# RJ-45_v1_1.net
KiCad netlist of a schematic drawn in EAGLE
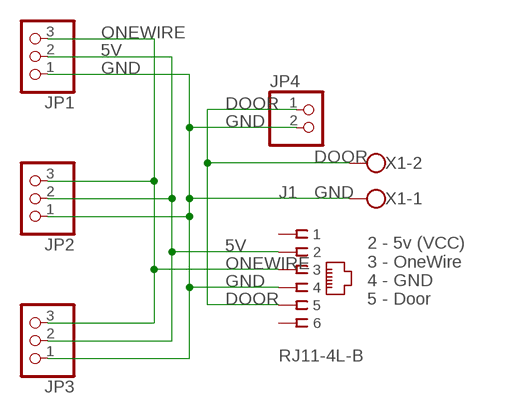
[diagram p0: schematic, sheet 1]

(export (version "E")
  (design (tool "Eeschema 10.0.6"))
  (components
    (comp (ref "J1")
      (value "RJ11-4L-B")
      (footprint "eagle-import:RJ11-NO_SHIELD")
      (fields (field (name "MF") "TYCO ELECTRONICS"))
      (libsource (lib "eagle-import") (part "RJ11-4L-B"))
    )
    (comp (ref "JP1")
      (value "PINHD-1X3")
      (footprint "eagle-import:1X03")
      (libsource (lib "eagle-import") (part "PINHD-1X3"))
    )
    (comp (ref "JP2")
      (value "PINHD-1X3")
      (footprint "eagle-import:1X03")
      (libsource (lib "eagle-import") (part "PINHD-1X3"))
    )
    (comp (ref "JP3")
      (value "PINHD-1X3")
      (footprint "eagle-import:1X03")
      (libsource (lib "eagle-import") (part "PINHD-1X3"))
    )
    (comp (ref "JP4")
      (value "PINHD-1X2")
      (footprint "eagle-import:1X02")
      (libsource (lib "eagle-import") (part "PINHD-1X2"))
    )
    (comp (ref "X1")
      (value "W237-102")
      (footprint "eagle-import:W237-102")
      (fields (field (name "MPN") "237-102"))
      (libsource (lib "eagle-import") (part "W237-102"))
    )
  )
  (nets
    (net (code "1") (name "/5V") (class "Default")
      (node (ref "J1") (pin "2") (pinfunction "2_2") (pintype "passive"))
      (node (ref "JP1") (pin "2") (pinfunction "2_2") (pintype "passive"))
      (node (ref "JP2") (pin "2") (pinfunction "2_2") (pintype "passive"))
      (node (ref "JP3") (pin "2") (pinfunction "2_2") (pintype "passive"))
    )
    (net (code "2") (name "/DOOR") (class "Default")
      (node (ref "J1") (pin "5") (pinfunction "5_5") (pintype "passive"))
      (node (ref "JP4") (pin "1") (pinfunction "1_1") (pintype "passive"))
      (node (ref "X1") (pin "2") (pinfunction "KL_2") (pintype "passive"))
    )
    (net (code "3") (name "/GND") (class "Default")
      (node (ref "J1") (pin "4") (pinfunction "4_4") (pintype "passive"))
      (node (ref "JP1") (pin "1") (pinfunction "1_1") (pintype "passive"))
      (node (ref "JP2") (pin "1") (pinfunction "1_1") (pintype "passive"))
      (node (ref "JP3") (pin "1") (pinfunction "1_1") (pintype "passive"))
      (node (ref "JP4") (pin "2") (pinfunction "2_2") (pintype "passive"))
      (node (ref "X1") (pin "1") (pinfunction "KL_1") (pintype "passive"))
    )
    (net (code "4") (name "/ONEWIRE") (class "Default")
      (node (ref "J1") (pin "3") (pinfunction "3_3") (pintype "passive"))
      (node (ref "JP1") (pin "3") (pinfunction "3_3") (pintype "passive"))
      (node (ref "JP2") (pin "3") (pinfunction "3_3") (pintype "passive"))
      (node (ref "JP3") (pin "3") (pinfunction "3_3") (pintype "passive"))
    )
    (net (code "5") (name "unconnected-(J1-Pad1)") (class "Default")
      (node (ref "J1") (pin "1") (pinfunction "1_1") (pintype "passive"))
    )
    (net (code "6") (name "unconnected-(J1-Pad6)") (class "Default")
      (node (ref "J1") (pin "6") (pinfunction "6_6") (pintype "passive"))
    )
  )
)
